# bpod_stepper_1_5_1.net
KiCad netlist of a schematic drawn in EAGLE
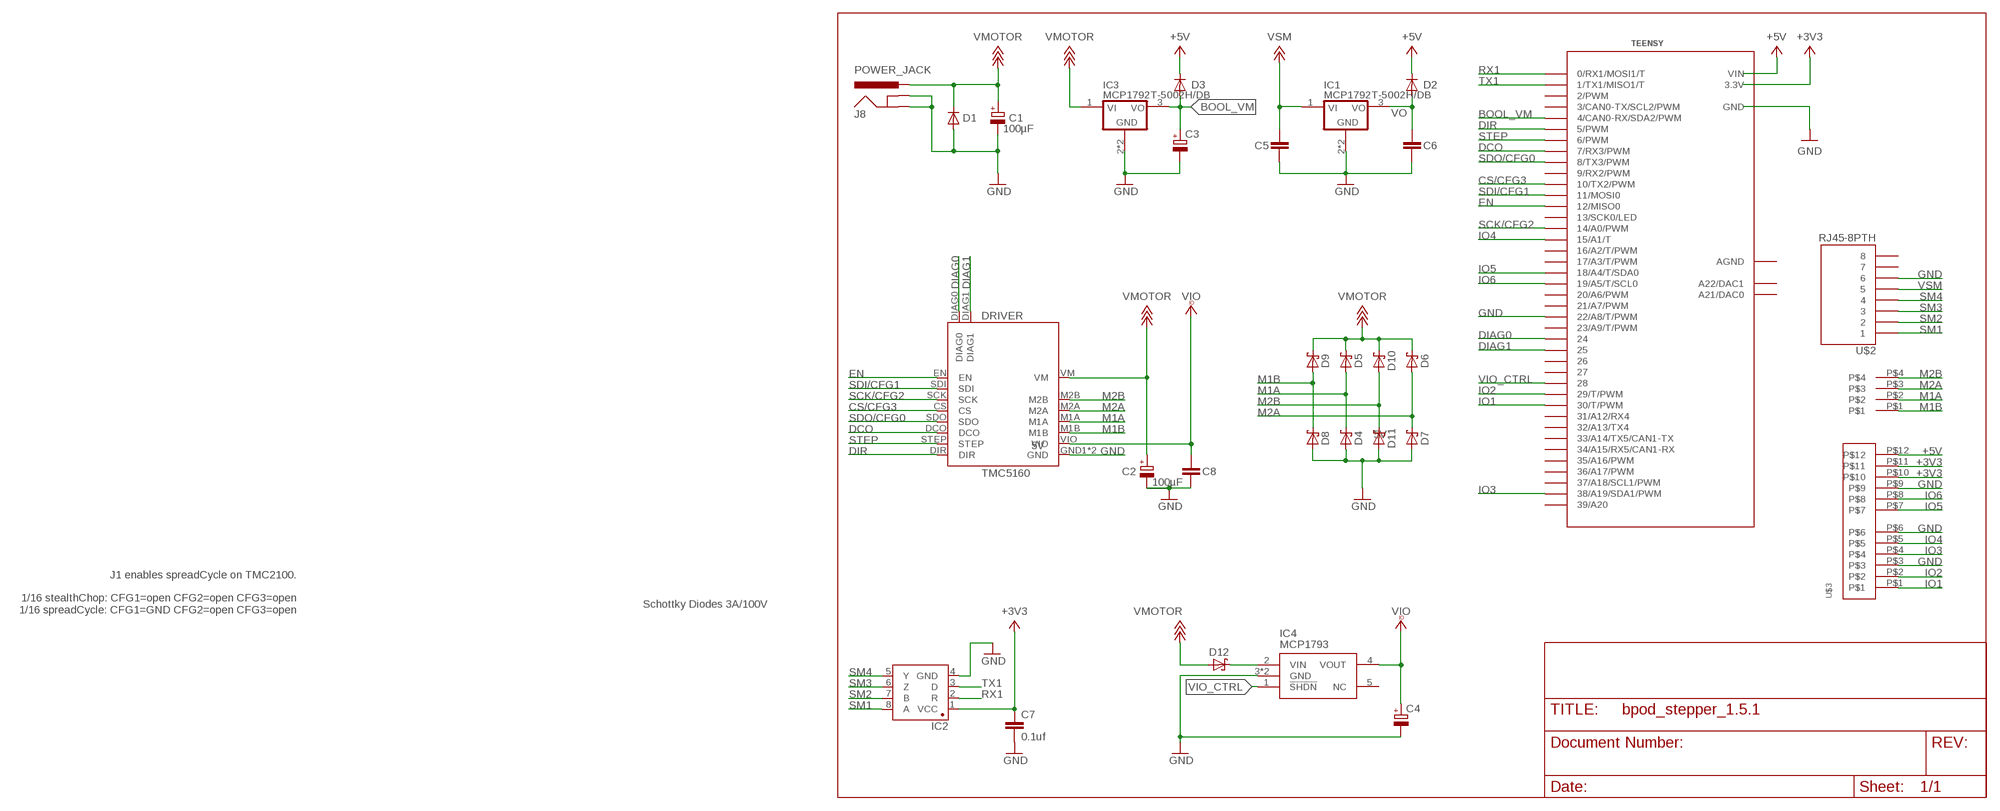
[diagram p0: schematic, sheet 1]

(export (version "E")
  (design (tool "Eeschema 10.0.6"))
  (components
    (comp (ref "C1")
      (value "100µF")
      (footprint "eagle-import:PANASONIC_G")
      (libsource (lib "eagle-import") (part "CPOL-EUG"))
    )
    (comp (ref "C2")
      (value "100µF")
      (footprint "eagle-import:PANASONIC_G")
      (libsource (lib "eagle-import") (part "CPOL-EUG"))
    )
    (comp (ref "C3")
      (value "CPOL-EUB")
      (footprint "eagle-import:PANASONIC_B")
      (libsource (lib "eagle-import") (part "CPOL-EUB"))
    )
    (comp (ref "C4")
      (value "CPOL-EUB")
      (footprint "eagle-import:PANASONIC_B")
      (libsource (lib "eagle-import") (part "CPOL-EUB"))
    )
    (comp (ref "C5")
      (value "0.1uf")
      (footprint "eagle-import:1206@1")
      (libsource (lib "eagle-import") (part "CAP1206"))
    )
    (comp (ref "C6")
      (value "0.1uf")
      (footprint "eagle-import:1206@1")
      (libsource (lib "eagle-import") (part "CAP1206"))
    )
    (comp (ref "C7")
      (value "0.1uf")
      (footprint "eagle-import:1206@1")
      (libsource (lib "eagle-import") (part "CAP1206"))
    )
    (comp (ref "C8")
      (value "100nf")
      (footprint "eagle-import:1206@1")
      (libsource (lib "eagle-import") (part "CAP1206"))
    )
    (comp (ref "D1")
      (value "DIODE-DO214AA")
      (footprint "eagle-import:DO214AA")
      (libsource (lib "eagle-import") (part "DIODE-DO214AA"))
    )
    (comp (ref "D2")
      (value "MBR0520LT")
      (footprint "eagle-import:SOD123")
      (libsource (lib "eagle-import") (part "MBR0520LT"))
    )
    (comp (ref "D3")
      (value "MBR0520LT")
      (footprint "eagle-import:SOD123")
      (libsource (lib "eagle-import") (part "MBR0520LT"))
    )
    (comp (ref "D4")
      (value "S310FA")
      (footprint "eagle-import:SOD123")
      (libsource (lib "eagle-import") (part "D_SCHOTTKY-SOD123"))
    )
    (comp (ref "D5")
      (value "S310FA")
      (footprint "eagle-import:SOD123")
      (libsource (lib "eagle-import") (part "D_SCHOTTKY-SOD123"))
    )
    (comp (ref "D6")
      (value "S310FA")
      (footprint "eagle-import:SOD123")
      (libsource (lib "eagle-import") (part "D_SCHOTTKY-SOD123"))
    )
    (comp (ref "D7")
      (value "S310FA")
      (footprint "eagle-import:SOD123")
      (libsource (lib "eagle-import") (part "D_SCHOTTKY-SOD123"))
    )
    (comp (ref "D8")
      (value "S310FA")
      (footprint "eagle-import:SOD123")
      (libsource (lib "eagle-import") (part "D_SCHOTTKY-SOD123"))
    )
    (comp (ref "D9")
      (value "S310FA")
      (footprint "eagle-import:SOD123")
      (libsource (lib "eagle-import") (part "D_SCHOTTKY-SOD123"))
    )
    (comp (ref "D10")
      (value "S310FA")
      (footprint "eagle-import:SOD123")
      (libsource (lib "eagle-import") (part "D_SCHOTTKY-SOD123"))
    )
    (comp (ref "D11")
      (value "S310FA")
      (footprint "eagle-import:SOD123")
      (libsource (lib "eagle-import") (part "D_SCHOTTKY-SOD123"))
    )
    (comp (ref "D12")
      (value "S310FA")
      (footprint "eagle-import:SOD123")
      (libsource (lib "eagle-import") (part "D_SCHOTTKY-SOD123"))
    )
    (comp (ref "DRIVER")
      (value "TMC5160")
      (footprint "eagle-import:TMC5160")
      (libsource (lib "eagle-import") (part "TMC5160"))
    )
    (comp (ref "IC1")
      (value "MCP1792T-5002H/DB")
      (footprint "eagle-import:SOT223")
      (libsource (lib "eagle-import") (part "MCP1792T-5002H/DB"))
    )
    (comp (ref "IC2")
      (value "SN65HVD31DR")
      (footprint "eagle-import:SO08")
      (libsource (lib "eagle-import") (part "SN65HVD31DR"))
    )
    (comp (ref "IC3")
      (value "MCP1792T-5002H/DB")
      (footprint "eagle-import:SOT223")
      (libsource (lib "eagle-import") (part "MCP1792T-5002H/DB"))
    )
    (comp (ref "IC4")
      (value "MCP1793")
      (footprint "eagle-import:SOT223-5")
      (libsource (lib "eagle-import") (part "MCP1793_SOT223-5"))
    )
    (comp (ref "J8")
      (value "POWER_JACK")
      (footprint "eagle-import:POWER_JACK_PTH")
      (libsource (lib "eagle-import") (part "POWER_JACK"))
    )
    (comp (ref "TEENSY")
      (value "TEENSY_3.6_DIL")
      (footprint "eagle-import:TEENSY_3.6_DIL")
      (libsource (lib "eagle-import") (part "TEENSY_3.6_DIL"))
    )
    (comp (ref "U$2")
      (value "RJ45-8PTH")
      (footprint "eagle-import:RJ45-8")
      (libsource (lib "eagle-import") (part "RJ45-8PTH"))
    )
    (comp (ref "U$3")
      (value "12POS_MOLEX_SOCKET")
      (footprint "eagle-import:12POS_MOLEX_SOCKET")
      (libsource (lib "eagle-import") (part "12POS_MOLEX_SOCKET"))
    )
    (comp (ref "U$4")
      (value "MOLEX395221004")
      (footprint "eagle-import:MOLEX395221004")
      (libsource (lib "eagle-import") (part "MOLEX395221004"))
    )
  )
  (nets
    (net (code "1") (name "+3V3") (class "Default")
      (node (ref "C7") (pin "1") (pinfunction "1_1") (pintype "passive"))
      (node (ref "IC2") (pin "1") (pinfunction "VCC_1") (pintype "bidirectional"))
      (node (ref "TEENSY") (pin "3.3V") (pinfunction "3.3V_3.3V") (pintype "power_in"))
      (node (ref "TEENSY") (pin "3.3V3") (pinfunction "3.3V_3.3V3") (pintype "power_in"))
      (node (ref "U$3") (pin "P$10") (pinfunction "P$10_P$10") (pintype "bidirectional"))
      (node (ref "U$3") (pin "P$11") (pinfunction "P$11_P$11") (pintype "bidirectional"))
    )
    (net (code "2") (name "+5V") (class "Default")
      (node (ref "D2") (pin "C") (pinfunction "C_C") (pintype "passive"))
      (node (ref "D3") (pin "C") (pinfunction "C_C") (pintype "passive"))
      (node (ref "TEENSY") (pin "VIN") (pinfunction "VIN_VIN") (pintype "power_in"))
      (node (ref "U$3") (pin "P$12") (pinfunction "P$12_P$12") (pintype "bidirectional"))
    )
    (net (code "3") (name "+12V") (class "Default")
      (node (ref "C5") (pin "2") (pinfunction "2_2") (pintype "passive"))
      (node (ref "IC1") (pin "1") (pinfunction "VI_1") (pintype "power_in"))
      (node (ref "U$2") (pin "5") (pinfunction "5_5") (pintype "bidirectional"))
    )
    (net (code "4") (name "+18V") (class "Default")
      (node (ref "C1") (pin "+") (pinfunction "+_+") (pintype "passive"))
      (node (ref "C2") (pin "+") (pinfunction "+_+") (pintype "passive"))
      (node (ref "D1") (pin "C") (pinfunction "C_C") (pintype "passive"))
      (node (ref "D10") (pin "C") (pinfunction "C_C") (pintype "passive"))
      (node (ref "D12") (pin "A") (pinfunction "A_A") (pintype "passive"))
      (node (ref "D5") (pin "C") (pinfunction "C_C") (pintype "passive"))
      (node (ref "D6") (pin "C") (pinfunction "C_C") (pintype "passive"))
      (node (ref "D9") (pin "C") (pinfunction "C_C") (pintype "passive"))
      (node (ref "DRIVER") (pin "VM") (pinfunction "VM_VM") (pintype "power_in"))
      (node (ref "IC3") (pin "1") (pinfunction "VI_1") (pintype "power_in"))
      (node (ref "J8") (pin "PWR") (pinfunction "PWR_PWR") (pintype "bidirectional"))
    )
    (net (code "5") (name "/AGND") (class "Default")
      (node (ref "TEENSY") (pin "AGND") (pinfunction "AGND_AGND") (pintype "power_in"))
    )
    (net (code "6") (name "/CS{slash}CFG3") (class "Default")
      (node (ref "DRIVER") (pin "CS") (pinfunction "CS_CS") (pintype "passive"))
      (node (ref "TEENSY") (pin "10") (pinfunction "10/TX2/PWM_10") (pintype "bidirectional"))
    )
    (net (code "7") (name "/DCO") (class "Default")
      (node (ref "DRIVER") (pin "DCO") (pinfunction "DCO_DCO") (pintype "passive"))
      (node (ref "TEENSY") (pin "7") (pinfunction "7/RX3/PWM_7") (pintype "bidirectional"))
    )
    (net (code "8") (name "/DIAG0") (class "Default")
      (node (ref "DRIVER") (pin "DIAG0") (pinfunction "DIAG0_DIAG0") (pintype "passive"))
      (node (ref "TEENSY") (pin "24") (pinfunction "24_24") (pintype "bidirectional"))
    )
    (net (code "9") (name "/DIAG1") (class "Default")
      (node (ref "DRIVER") (pin "DIAG1") (pinfunction "DIAG1_DIAG1") (pintype "passive"))
      (node (ref "TEENSY") (pin "25") (pinfunction "25_25") (pintype "bidirectional"))
    )
    (net (code "10") (name "/DIR") (class "Default")
      (node (ref "DRIVER") (pin "DIR") (pinfunction "DIR_DIR") (pintype "input"))
      (node (ref "TEENSY") (pin "5") (pinfunction "5/PWM_5") (pintype "bidirectional"))
    )
    (net (code "11") (name "/EN") (class "Default")
      (node (ref "DRIVER") (pin "EN") (pinfunction "EN_EN") (pintype "passive"))
      (node (ref "TEENSY") (pin "12") (pinfunction "12/MISO0_12") (pintype "bidirectional"))
    )
    (net (code "12") (name "/IO1") (class "Default")
      (node (ref "TEENSY") (pin "30") (pinfunction "30/T/PWM_30") (pintype "bidirectional"))
      (node (ref "U$3") (pin "P$1") (pinfunction "P$1_P$1") (pintype "bidirectional"))
    )
    (net (code "13") (name "/IO2") (class "Default")
      (node (ref "TEENSY") (pin "29") (pinfunction "29/T/PWM_29") (pintype "bidirectional"))
      (node (ref "U$3") (pin "P$2") (pinfunction "P$2_P$2") (pintype "bidirectional"))
    )
    (net (code "14") (name "/IO3") (class "Default")
      (node (ref "TEENSY") (pin "38/A19") (pinfunction "38/A19/SDA1/PWM_38/A19") (pintype "bidirectional"))
      (node (ref "U$3") (pin "P$4") (pinfunction "P$4_P$4") (pintype "bidirectional"))
    )
    (net (code "15") (name "/IO4") (class "Default")
      (node (ref "TEENSY") (pin "15/A1") (pinfunction "15/A1/T_15/A1") (pintype "bidirectional"))
      (node (ref "U$3") (pin "P$5") (pinfunction "P$5_P$5") (pintype "bidirectional"))
    )
    (net (code "16") (name "/IO5") (class "Default")
      (node (ref "TEENSY") (pin "18/A4") (pinfunction "18/A4/T/SDA0_18/A4") (pintype "bidirectional"))
      (node (ref "U$3") (pin "P$7") (pinfunction "P$7_P$7") (pintype "bidirectional"))
    )
    (net (code "17") (name "/IO6") (class "Default")
      (node (ref "TEENSY") (pin "19/A5") (pinfunction "19/A5/T/SCL0_19/A5") (pintype "bidirectional"))
      (node (ref "U$3") (pin "P$8") (pinfunction "P$8_P$8") (pintype "bidirectional"))
    )
    (net (code "18") (name "/M1A") (class "Default")
      (node (ref "D4") (pin "C") (pinfunction "C_C") (pintype "passive"))
      (node (ref "D5") (pin "A") (pinfunction "A_A") (pintype "passive"))
      (node (ref "DRIVER") (pin "M1A") (pinfunction "M1A_M1A") (pintype "output"))
      (node (ref "U$4") (pin "P$2") (pinfunction "P$2_P$2") (pintype "bidirectional"))
    )
    (net (code "19") (name "/M1B") (class "Default")
      (node (ref "D8") (pin "C") (pinfunction "C_C") (pintype "passive"))
      (node (ref "D9") (pin "A") (pinfunction "A_A") (pintype "passive"))
      (node (ref "DRIVER") (pin "M1B") (pinfunction "M1B_M1B") (pintype "output"))
      (node (ref "U$4") (pin "P$1") (pinfunction "P$1_P$1") (pintype "bidirectional"))
    )
    (net (code "20") (name "/M2A") (class "Default")
      (node (ref "D6") (pin "A") (pinfunction "A_A") (pintype "passive"))
      (node (ref "D7") (pin "C") (pinfunction "C_C") (pintype "passive"))
      (node (ref "DRIVER") (pin "M2A") (pinfunction "M2A_M2A") (pintype "output"))
      (node (ref "U$4") (pin "P$3") (pinfunction "P$3_P$3") (pintype "bidirectional"))
    )
    (net (code "21") (name "/M2B") (class "Default")
      (node (ref "D10") (pin "A") (pinfunction "A_A") (pintype "passive"))
      (node (ref "D11") (pin "C") (pinfunction "C_C") (pintype "passive"))
      (node (ref "DRIVER") (pin "M2B") (pinfunction "M2B_M2B") (pintype "output"))
      (node (ref "U$4") (pin "P$4") (pinfunction "P$4_P$4") (pintype "bidirectional"))
    )
    (net (code "22") (name "/RX1") (class "Default")
      (node (ref "IC2") (pin "2") (pinfunction "R_2") (pintype "bidirectional"))
      (node (ref "TEENSY") (pin "0") (pinfunction "0/RX1/MOSI1/T_0") (pintype "bidirectional"))
    )
    (net (code "23") (name "/SCK{slash}CFG2") (class "Default")
      (node (ref "DRIVER") (pin "SCK") (pinfunction "SCK_SCK") (pintype "passive"))
      (node (ref "TEENSY") (pin "14/A0") (pinfunction "14/A0/PWM_14/A0") (pintype "bidirectional"))
    )
    (net (code "24") (name "/SDI{slash}CFG1") (class "Default")
      (node (ref "DRIVER") (pin "SDI") (pinfunction "SDI_SDI") (pintype "passive"))
      (node (ref "TEENSY") (pin "11") (pinfunction "11/MOSI0_11") (pintype "bidirectional"))
    )
    (net (code "25") (name "/SDO{slash}CFG0") (class "Default")
      (node (ref "DRIVER") (pin "SDO") (pinfunction "SDO_SDO") (pintype "passive"))
      (node (ref "TEENSY") (pin "8") (pinfunction "8/TX3/PWM_8") (pintype "bidirectional"))
    )
    (net (code "26") (name "/SM1") (class "Default")
      (node (ref "IC2") (pin "8") (pinfunction "A_8") (pintype "bidirectional"))
      (node (ref "U$2") (pin "1") (pinfunction "1_1") (pintype "bidirectional"))
    )
    (net (code "27") (name "/SM2") (class "Default")
      (node (ref "IC2") (pin "7") (pinfunction "B_7") (pintype "bidirectional"))
      (node (ref "U$2") (pin "2") (pinfunction "2_2") (pintype "bidirectional"))
    )
    (net (code "28") (name "/SM3") (class "Default")
      (node (ref "IC2") (pin "6") (pinfunction "Z_6") (pintype "bidirectional"))
      (node (ref "U$2") (pin "3") (pinfunction "3_3") (pintype "bidirectional"))
    )
    (net (code "29") (name "/SM4") (class "Default")
      (node (ref "IC2") (pin "5") (pinfunction "Y_5") (pintype "bidirectional"))
      (node (ref "U$2") (pin "4") (pinfunction "4_4") (pintype "bidirectional"))
    )
    (net (code "30") (name "/STEP") (class "Default")
      (node (ref "DRIVER") (pin "STEP") (pinfunction "STEP_STEP") (pintype "input"))
      (node (ref "TEENSY") (pin "6") (pinfunction "6/PWM_6") (pintype "bidirectional"))
    )
    (net (code "31") (name "/TX1") (class "Default")
      (node (ref "IC2") (pin "3") (pinfunction "D_3") (pintype "bidirectional"))
      (node (ref "TEENSY") (pin "1") (pinfunction "1/TX1/MISO1/T_1") (pintype "bidirectional"))
    )
    (net (code "32") (name "/VO") (class "Default")
      (node (ref "C6") (pin "2") (pinfunction "2_2") (pintype "passive"))
      (node (ref "D2") (pin "A") (pinfunction "A_A") (pintype "passive"))
      (node (ref "IC1") (pin "3") (pinfunction "VO_3") (pintype "passive"))
    )
    (net (code "33") (name "BOOL_VM") (class "Default")
      (node (ref "C3") (pin "+") (pinfunction "+_+") (pintype "passive"))
      (node (ref "D3") (pin "A") (pinfunction "A_A") (pintype "passive"))
      (node (ref "IC3") (pin "3") (pinfunction "VO_3") (pintype "passive"))
      (node (ref "TEENSY") (pin "4") (pinfunction "4/CAN0-RX/SDA2/PWM_4") (pintype "bidirectional"))
    )
    (net (code "34") (name "GND") (class "Default")
      (node (ref "C1") (pin "-") (pinfunction "-_-") (pintype "passive"))
      (node (ref "C2") (pin "-") (pinfunction "-_-") (pintype "passive"))
      (node (ref "C3") (pin "-") (pinfunction "-_-") (pintype "passive"))
      (node (ref "C4") (pin "-") (pinfunction "-_-") (pintype "passive"))
      (node (ref "C5") (pin "1") (pinfunction "1_1") (pintype "passive"))
      (node (ref "C6") (pin "1") (pinfunction "1_1") (pintype "passive"))
      (node (ref "C7") (pin "2") (pinfunction "2_2") (pintype "passive"))
      (node (ref "C8") (pin "2") (pinfunction "2_2") (pintype "passive"))
      (node (ref "D1") (pin "A") (pinfunction "A_A") (pintype "passive"))
      (node (ref "D11") (pin "A") (pinfunction "A_A") (pintype "passive"))
      (node (ref "D4") (pin "A") (pinfunction "A_A") (pintype "passive"))
      (node (ref "D7") (pin "A") (pinfunction "A_A") (pintype "passive"))
      (node (ref "D8") (pin "A") (pinfunction "A_A") (pintype "passive"))
      (node (ref "DRIVER") (pin "GND1") (pinfunction "GND_GND1") (pintype "power_in"))
      (node (ref "DRIVER") (pin "GND2") (pinfunction "GND_GND2") (pintype "power_in"))
      (node (ref "IC1") (pin "2") (pinfunction "GND_2") (pintype "power_in"))
      (node (ref "IC1") (pin "4") (pinfunction "GND_4") (pintype "power_in"))
      (node (ref "IC2") (pin "4") (pinfunction "GND_4") (pintype "bidirectional"))
      (node (ref "IC3") (pin "2") (pinfunction "GND_2") (pintype "power_in"))
      (node (ref "IC3") (pin "4") (pinfunction "GND_4") (pintype "power_in"))
      (node (ref "IC4") (pin "3") (pinfunction "GND_3") (pintype "bidirectional"))
      (node (ref "IC4") (pin "6") (pinfunction "GND_6") (pintype "bidirectional"))
      (node (ref "J8") (pin "GND") (pinfunction "GND_GND") (pintype "bidirectional"))
      (node (ref "J8") (pin "GNDBREAK") (pinfunction "GNDBREAK_GNDBREAK") (pintype "bidirectional"))
      (node (ref "TEENSY") (pin "22/A8") (pinfunction "22/A8/T/PWM_22/A8") (pintype "bidirectional"))
      (node (ref "TEENSY") (pin "GND") (pinfunction "GND_GND") (pintype "power_in"))
      (node (ref "TEENSY") (pin "GND1") (pinfunction "GND_GND1") (pintype "power_in"))
      (node (ref "U$2") (pin "6") (pinfunction "6_6") (pintype "bidirectional"))
      (node (ref "U$3") (pin "P$3") (pinfunction "P$3_P$3") (pintype "bidirectional"))
      (node (ref "U$3") (pin "P$6") (pinfunction "P$6_P$6") (pintype "bidirectional"))
      (node (ref "U$3") (pin "P$9") (pinfunction "P$9_P$9") (pintype "bidirectional"))
    )
    (net (code "35") (name "Net-(IC4-VIN)") (class "Default")
      (node (ref "D12") (pin "C") (pinfunction "C_C") (pintype "passive"))
      (node (ref "IC4") (pin "2") (pinfunction "VIN_2") (pintype "bidirectional"))
    )
    (net (code "36") (name "VCCIO") (class "Default")
      (node (ref "C4") (pin "+") (pinfunction "+_+") (pintype "passive"))
      (node (ref "C8") (pin "1") (pinfunction "1_1") (pintype "passive"))
      (node (ref "DRIVER") (pin "VIO") (pinfunction "VIO_VIO") (pintype "power_in"))
      (node (ref "IC4") (pin "4") (pinfunction "VOUT_4") (pintype "bidirectional"))
    )
    (net (code "37") (name "VIO_CTRL") (class "Default")
      (node (ref "IC4") (pin "1") (pinfunction "~{SHDN}_1") (pintype "bidirectional"))
      (node (ref "TEENSY") (pin "28") (pinfunction "28_28") (pintype "bidirectional"))
    )
    (net (code "38") (name "unconnected-(IC4-NC-Pad5)") (class "Default")
      (node (ref "IC4") (pin "5") (pinfunction "NC_5") (pintype "bidirectional"))
    )
    (net (code "39") (name "unconnected-(TEENSY-2{slash}PWM-Pad2)") (class "Default")
      (node (ref "TEENSY") (pin "2") (pinfunction "2/PWM_2") (pintype "bidirectional"))
    )
    (net (code "40") (name "unconnected-(TEENSY-3{slash}CAN0-TX{slash}SCL2{slash}PWM-Pad3)") (class "Default")
      (node (ref "TEENSY") (pin "3") (pinfunction "3/CAN0-TX/SCL2/PWM_3") (pintype "bidirectional"))
    )
    (net (code "41") (name "unconnected-(TEENSY-9{slash}RX2{slash}PWM-Pad9)") (class "Default")
      (node (ref "TEENSY") (pin "9") (pinfunction "9/RX2/PWM_9") (pintype "bidirectional"))
    )
    (net (code "42") (name "unconnected-(TEENSY-13{slash}SCK0{slash}LED-Pad13)") (class "Default")
      (node (ref "TEENSY") (pin "13") (pinfunction "13/SCK0/LED_13") (pintype "bidirectional"))
    )
    (net (code "43") (name "unconnected-(TEENSY-16{slash}A2{slash}T{slash}PWM-Pad16{slash}A2)") (class "Default")
      (node (ref "TEENSY") (pin "16/A2") (pinfunction "16/A2/T/PWM_16/A2") (pintype "bidirectional"))
    )
    (net (code "44") (name "unconnected-(TEENSY-17{slash}A3{slash}T{slash}PWM-Pad17{slash}A3)") (class "Default")
      (node (ref "TEENSY") (pin "17/A3") (pinfunction "17/A3/T/PWM_17/A3") (pintype "bidirectional"))
    )
    (net (code "45") (name "unconnected-(TEENSY-20{slash}A6{slash}PWM-Pad20{slash}A6)") (class "Default")
      (node (ref "TEENSY") (pin "20/A6") (pinfunction "20/A6/PWM_20/A6") (pintype "bidirectional"))
    )
    (net (code "46") (name "unconnected-(TEENSY-21{slash}A7{slash}PWM-Pad21{slash}A7)") (class "Default")
      (node (ref "TEENSY") (pin "21/A7") (pinfunction "21/A7/PWM_21/A7") (pintype "bidirectional"))
    )
    (net (code "47") (name "unconnected-(TEENSY-23{slash}A9{slash}T{slash}PWM-Pad23{slash}A9)") (class "Default")
      (node (ref "TEENSY") (pin "23/A9") (pinfunction "23/A9/T/PWM_23/A9") (pintype "bidirectional"))
    )
    (net (code "48") (name "unconnected-(TEENSY-31{slash}A12{slash}RX4-Pad31{slash}A12)") (class "Default")
      (node (ref "TEENSY") (pin "31/A12") (pinfunction "31/A12/RX4_31/A12") (pintype "bidirectional"))
    )
    (net (code "49") (name "unconnected-(TEENSY-32{slash}A13{slash}TX4-Pad32{slash}A13)") (class "Default")
      (node (ref "TEENSY") (pin "32/A13") (pinfunction "32/A13/TX4_32/A13") (pintype "bidirectional"))
    )
    (net (code "50") (name "unconnected-(TEENSY-33{slash}A14{slash}TX5{slash}CAN1-TX-Pad33{slash}A14)") (class "Default")
      (node (ref "TEENSY") (pin "33/A14") (pinfunction "33/A14/TX5/CAN1-TX_33/A14") (pintype "bidirectional"))
    )
    (net (code "51") (name "unconnected-(TEENSY-34{slash}A15{slash}RX5{slash}CAN1-RX-Pad34{slash}A15)") (class "Default")
      (node (ref "TEENSY") (pin "34/A15") (pinfunction "34/A15/RX5/CAN1-RX_34/A15") (pintype "bidirectional"))
    )
    (net (code "52") (name "unconnected-(TEENSY-35{slash}A16{slash}PWM-Pad35{slash}A16)") (class "Default")
      (node (ref "TEENSY") (pin "35/A16") (pinfunction "35/A16/PWM_35/A16") (pintype "bidirectional"))
    )
    (net (code "53") (name "unconnected-(TEENSY-36{slash}A17{slash}PWM-Pad36{slash}A17)") (class "Default")
      (node (ref "TEENSY") (pin "36/A17") (pinfunction "36/A17/PWM_36/A17") (pintype "bidirectional"))
    )
    (net (code "54") (name "unconnected-(TEENSY-37{slash}A18{slash}SCL1{slash}PWM-Pad37{slash}A18)") (class "Default")
      (node (ref "TEENSY") (pin "37/A18") (pinfunction "37/A18/SCL1/PWM_37/A18") (pintype "bidirectional"))
    )
    (net (code "55") (name "unconnected-(TEENSY-A21{slash}DAC0-PadA21)") (class "Default")
      (node (ref "TEENSY") (pin "A21") (pinfunction "A21/DAC0_A21") (pintype "bidirectional"))
    )
    (net (code "56") (name "unconnected-(TEENSY-A22{slash}DAC1-PadA22)") (class "Default")
      (node (ref "TEENSY") (pin "A22") (pinfunction "A22/DAC1_A22") (pintype "bidirectional"))
    )
    (net (code "57") (name "unconnected-(TEENSY-Pad26)") (class "Default")
      (node (ref "TEENSY") (pin "26") (pinfunction "26_26") (pintype "bidirectional"))
    )
    (net (code "58") (name "unconnected-(TEENSY-Pad27)") (class "Default")
      (node (ref "TEENSY") (pin "27") (pinfunction "27_27") (pintype "bidirectional"))
    )
    (net (code "59") (name "unconnected-(TEENSY-Pad39{slash}A20)") (class "Default")
      (node (ref "TEENSY") (pin "39/A20") (pinfunction "39/A20_39/A20") (pintype "bidirectional"))
    )
    (net (code "60") (name "unconnected-(U$2-Pad7)") (class "Default")
      (node (ref "U$2") (pin "7") (pinfunction "7_7") (pintype "bidirectional"))
    )
    (net (code "61") (name "unconnected-(U$2-Pad8)") (class "Default")
      (node (ref "U$2") (pin "8") (pinfunction "8_8") (pintype "bidirectional"))
    )
  )
)
